# LoRaBaseBoard.net
KiCad netlist of a schematic drawn in EAGLE
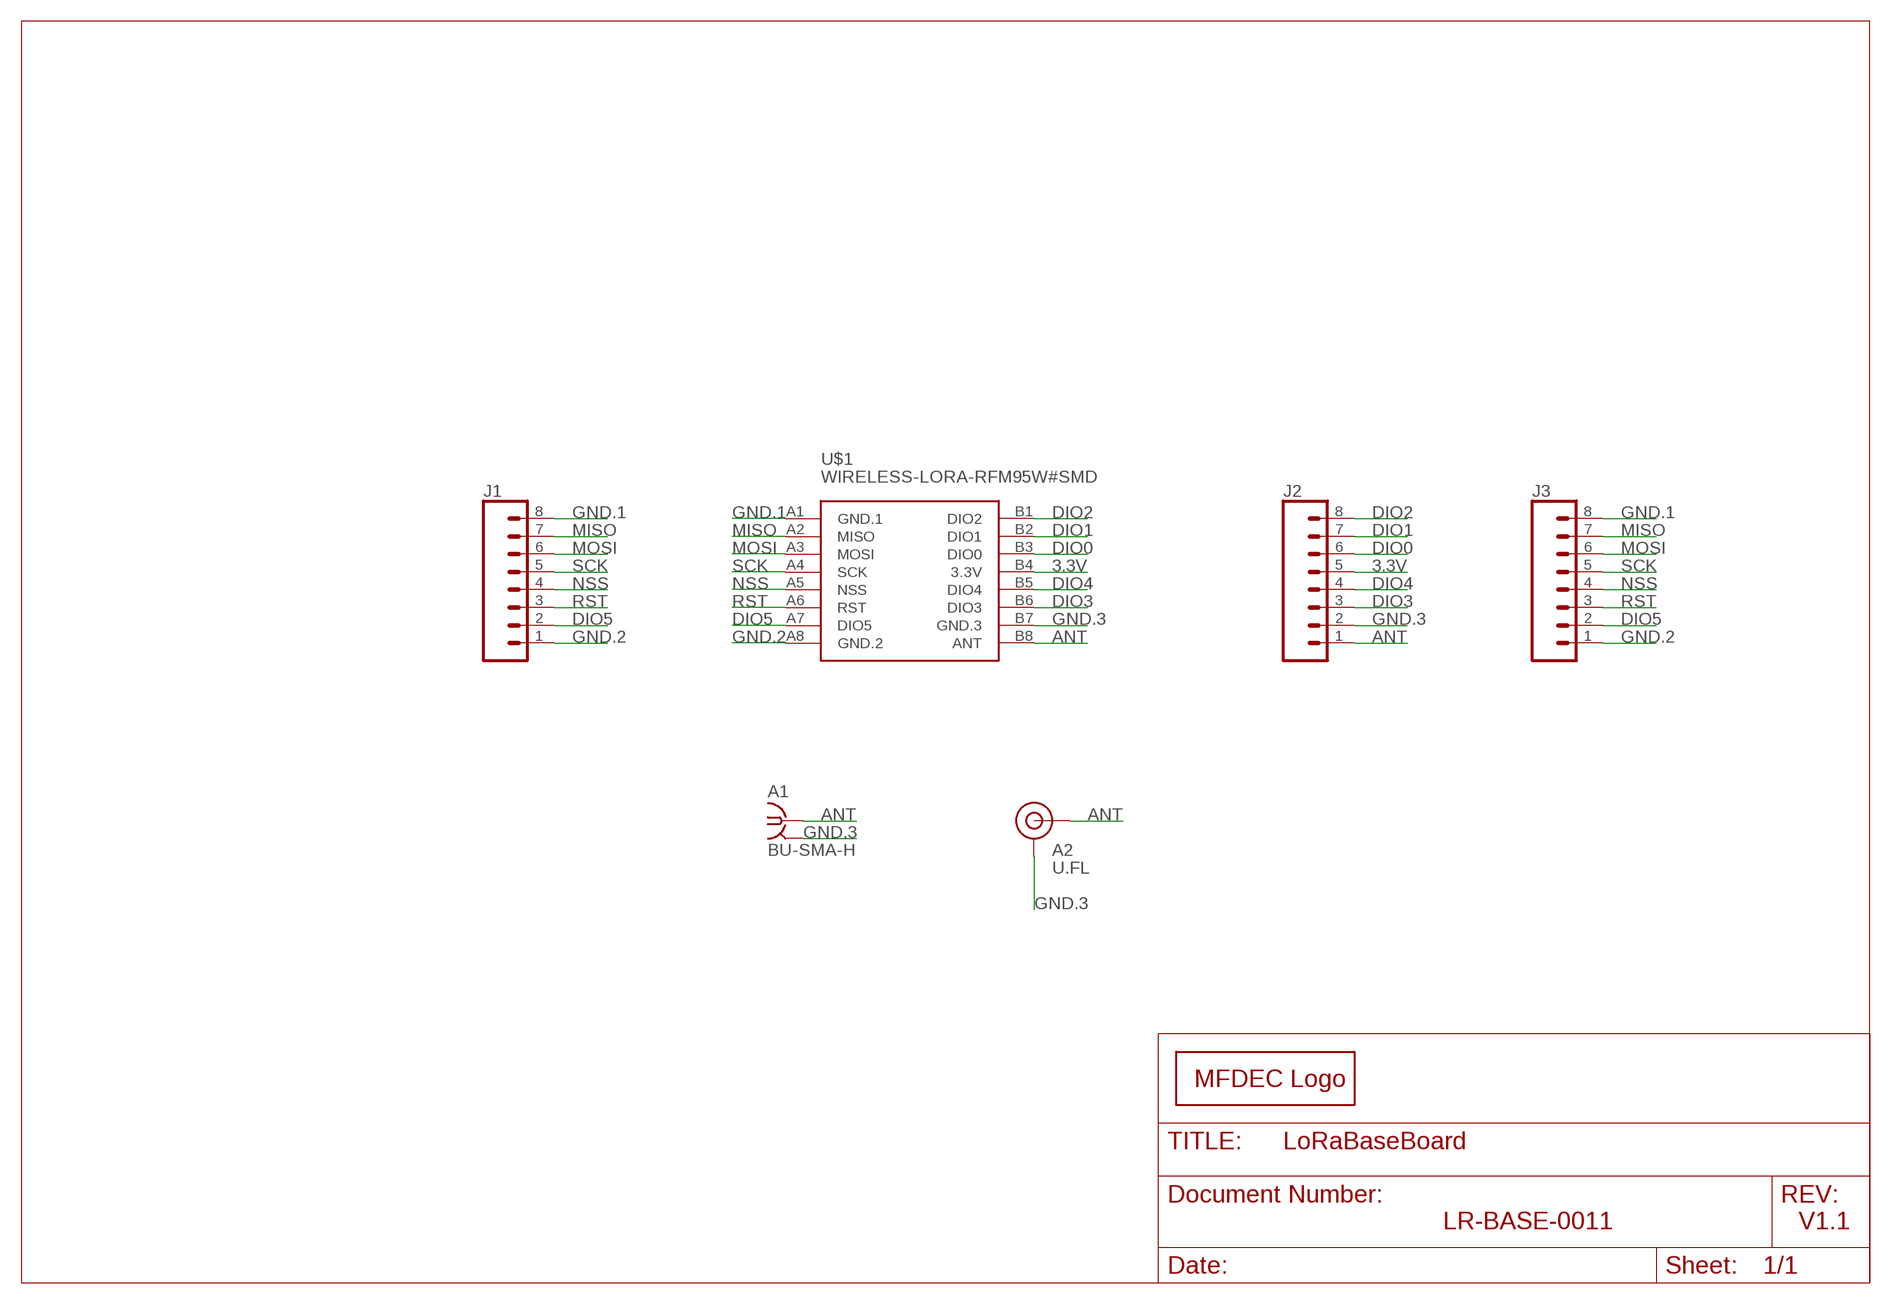
[diagram p0: schematic, sheet 1]

(export (version "E")
  (design (tool "Eeschema 10.0.6"))
  (components
    (comp (ref "A1")
      (value "BU-SMA-H")
      (footprint "eagle-import:BU-SMA-H")
      (libsource (lib "eagle-import") (part "BU-SMA-H"))
    )
    (comp (ref "A2")
      (value "U.FL")
      (footprint "eagle-import:U.FL")
      (libsource (lib "eagle-import") (part "U.FL2PIN"))
    )
    (comp (ref "J1")
      (value "CONN_08NO_SILK_FEMALE_PTH")
      (footprint "eagle-import:1X08_NO_SILK")
      (libsource (lib "eagle-import") (part "CONN_08NO_SILK_FEMALE_PTH"))
    )
    (comp (ref "J2")
      (value "CONN_08NO_SILK_FEMALE_PTH")
      (footprint "eagle-import:1X08_NO_SILK")
      (libsource (lib "eagle-import") (part "CONN_08NO_SILK_FEMALE_PTH"))
    )
    (comp (ref "J3")
      (value "CONN_08NO_SILK_FEMALE_PTH")
      (footprint "eagle-import:1X08_NO_SILK")
      (libsource (lib "eagle-import") (part "CONN_08NO_SILK_FEMALE_PTH"))
    )
    (comp (ref "LOGO1")
      (value "MFDECLOGO_SQ_8MM")
      (footprint "eagle-import:MFDEC_SQ_8MM")
      (libsource (lib "eagle-import") (part "MFDECLOGO_SQ_8MM"))
    )
    (comp (ref "U$1")
      (value "WIRELESS-LORA-RFM95W#SMD")
      (footprint "eagle-import:WIRELESS-LORA-RFM95W#SMD")
      (libsource (lib "eagle-import") (part "WIRELESS-LORA-RFM95W#SMD"))
    )
  )
  (nets
    (net (code "1") (name "/3.3V") (class "Default")
      (node (ref "J2") (pin "5") (pinfunction "5_5") (pintype "passive"))
      (node (ref "U$1") (pin "B4") (pinfunction "3.3V_B4") (pintype "power_in"))
    )
    (net (code "2") (name "/ANT") (class "Default")
      (node (ref "A1") (pin "1") (pinfunction "1_1") (pintype "passive"))
      (node (ref "A2") (pin "FEED") (pinfunction "SIGNAL_FEED") (pintype "bidirectional"))
      (node (ref "J2") (pin "1") (pinfunction "1_1") (pintype "passive"))
      (node (ref "U$1") (pin "B8") (pinfunction "ANT_B8") (pintype "passive"))
    )
    (net (code "3") (name "/DIO0") (class "Default")
      (node (ref "J2") (pin "6") (pinfunction "6_6") (pintype "passive"))
      (node (ref "U$1") (pin "B3") (pinfunction "DIO0_B3") (pintype "bidirectional"))
    )
    (net (code "4") (name "/DIO1") (class "Default")
      (node (ref "J2") (pin "7") (pinfunction "7_7") (pintype "passive"))
      (node (ref "U$1") (pin "B2") (pinfunction "DIO1_B2") (pintype "bidirectional"))
    )
    (net (code "5") (name "/DIO2") (class "Default")
      (node (ref "J2") (pin "8") (pinfunction "8_8") (pintype "passive"))
      (node (ref "U$1") (pin "B1") (pinfunction "DIO2_B1") (pintype "bidirectional"))
    )
    (net (code "6") (name "/DIO3") (class "Default")
      (node (ref "J2") (pin "3") (pinfunction "3_3") (pintype "passive"))
      (node (ref "U$1") (pin "B6") (pinfunction "DIO3_B6") (pintype "bidirectional"))
    )
    (net (code "7") (name "/DIO4") (class "Default")
      (node (ref "J2") (pin "4") (pinfunction "4_4") (pintype "passive"))
      (node (ref "U$1") (pin "B5") (pinfunction "DIO4_B5") (pintype "bidirectional"))
    )
    (net (code "8") (name "/DIO5") (class "Default")
      (node (ref "J1") (pin "2") (pinfunction "2_2") (pintype "passive"))
      (node (ref "J3") (pin "2") (pinfunction "2_2") (pintype "passive"))
      (node (ref "U$1") (pin "A7") (pinfunction "DIO5_A7") (pintype "bidirectional"))
    )
    (net (code "9") (name "/GND.1") (class "Default")
      (node (ref "J1") (pin "8") (pinfunction "8_8") (pintype "passive"))
      (node (ref "J3") (pin "8") (pinfunction "8_8") (pintype "passive"))
      (node (ref "U$1") (pin "A1") (pinfunction "GND.1_A1") (pintype "power_in"))
    )
    (net (code "10") (name "/GND.2") (class "Default")
      (node (ref "J1") (pin "1") (pinfunction "1_1") (pintype "passive"))
      (node (ref "J3") (pin "1") (pinfunction "1_1") (pintype "passive"))
      (node (ref "U$1") (pin "A8") (pinfunction "GND.2_A8") (pintype "power_in"))
    )
    (net (code "11") (name "/GND.3") (class "Default")
      (node (ref "A1") (pin "2") (pinfunction "2_2") (pintype "passive"))
      (node (ref "A1") (pin "3") (pinfunction "2_3") (pintype "passive"))
      (node (ref "A1") (pin "4") (pinfunction "2_4") (pintype "passive"))
      (node (ref "A1") (pin "5") (pinfunction "2_5") (pintype "passive"))
      (node (ref "A2") (pin "1") (pinfunction "GND_1") (pintype "bidirectional"))
      (node (ref "A2") (pin "2") (pinfunction "GND_2") (pintype "bidirectional"))
      (node (ref "J2") (pin "2") (pinfunction "2_2") (pintype "passive"))
      (node (ref "U$1") (pin "B7") (pinfunction "GND.3_B7") (pintype "power_in"))
    )
    (net (code "12") (name "/MISO") (class "Default")
      (node (ref "J1") (pin "7") (pinfunction "7_7") (pintype "passive"))
      (node (ref "J3") (pin "7") (pinfunction "7_7") (pintype "passive"))
      (node (ref "U$1") (pin "A2") (pinfunction "MISO_A2") (pintype "bidirectional"))
    )
    (net (code "13") (name "/MOSI") (class "Default")
      (node (ref "J1") (pin "6") (pinfunction "6_6") (pintype "passive"))
      (node (ref "J3") (pin "6") (pinfunction "6_6") (pintype "passive"))
      (node (ref "U$1") (pin "A3") (pinfunction "MOSI_A3") (pintype "bidirectional"))
    )
    (net (code "14") (name "/NSS") (class "Default")
      (node (ref "J1") (pin "4") (pinfunction "4_4") (pintype "passive"))
      (node (ref "J3") (pin "4") (pinfunction "4_4") (pintype "passive"))
      (node (ref "U$1") (pin "A5") (pinfunction "NSS_A5") (pintype "bidirectional"))
    )
    (net (code "15") (name "/RST") (class "Default")
      (node (ref "J1") (pin "3") (pinfunction "3_3") (pintype "passive"))
      (node (ref "J3") (pin "3") (pinfunction "3_3") (pintype "passive"))
      (node (ref "U$1") (pin "A6") (pinfunction "RST_A6") (pintype "bidirectional"))
    )
    (net (code "16") (name "/SCK") (class "Default")
      (node (ref "J1") (pin "5") (pinfunction "5_5") (pintype "passive"))
      (node (ref "J3") (pin "5") (pinfunction "5_5") (pintype "passive"))
      (node (ref "U$1") (pin "A4") (pinfunction "SCK_A4") (pintype "bidirectional"))
    )
  )
)
